# POWER_CORE.net
KiCad netlist of a schematic drawn in Altium Designer
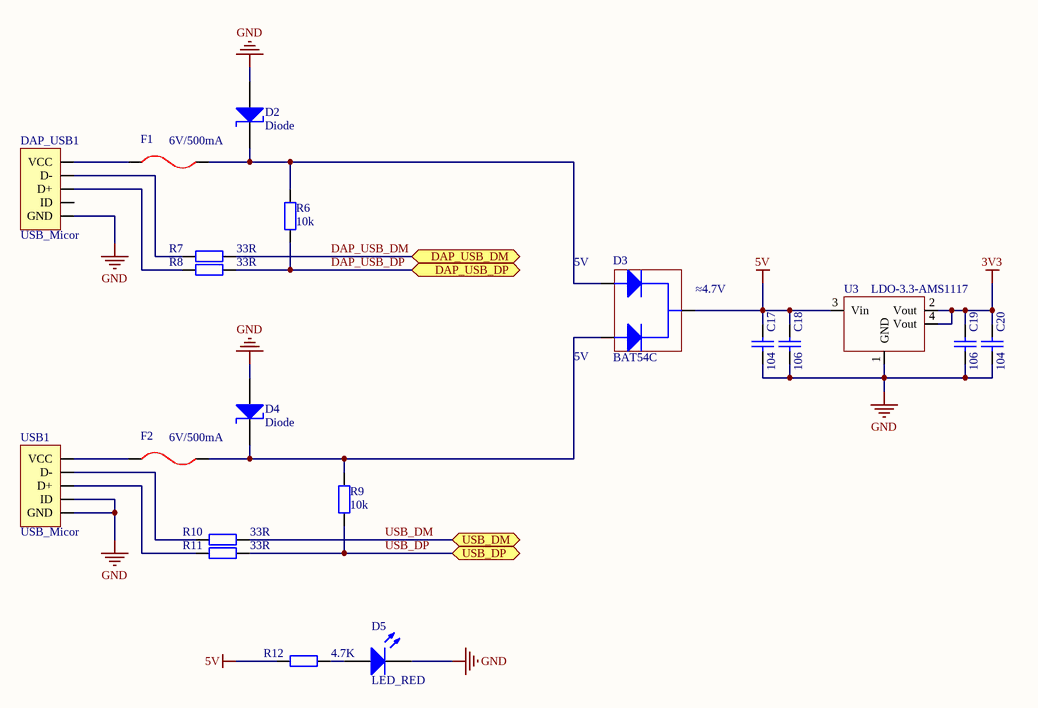
[diagram p0: POWER_CORE.SchDoc]

(export (version "E")
  (design (tool "Eeschema 10.0.6"))
  (components
    (comp (ref "C17")
      (value "104")
      (footprint "C_SOP_0603")
      (description "电容_无极性")
      (libsource (lib "lib-base") (part "Cap"))
    )
    (comp (ref "C18")
      (value "106")
      (footprint "C_SOP_0603")
      (description "电容_无极性")
      (libsource (lib "lib-base") (part "Cap"))
    )
    (comp (ref "C19")
      (value "106")
      (footprint "C_SOP_0603")
      (description "电容_无极性")
      (libsource (lib "lib-base") (part "Cap"))
    )
    (comp (ref "C20")
      (value "104")
      (footprint "C_SOP_0603")
      (description "电容_无极性")
      (libsource (lib "lib-base") (part "Cap"))
    )
    (comp (ref "D2")
      (value "Diode")
      (footprint "SOD-123")
      (description "肖特基二极管\r\n1N4007、SS24")
      (libsource (lib "lib-base") (part "Diode"))
    )
    (comp (ref "D3")
      (value "BAT54C")
      (footprint "SOT23_3")
      (description "肖特基二极管*2")
      (libsource (lib "lib-base") (part "BAT54C"))
    )
    (comp (ref "D4")
      (value "Diode")
      (footprint "SOD-123")
      (description "肖特基二极管\r\n1N4007、SS24")
      (libsource (lib "lib-base") (part "Diode"))
    )
    (comp (ref "D5")
      (value "LED_RED")
      (footprint "LED_0603_R")
      (description "发光二极管")
      (libsource (lib "lib-base") (part "LED"))
    )
    (comp (ref "DAP_USB1")
      (value "USB_Micor")
      (footprint "USB_Micor")
      (libsource (lib "lib-con") (part "USB_Micor"))
    )
    (comp (ref "F1")
      (value "6V/500mA")
      (footprint "FUSE_0603")
      (description "自恢复保险丝")
      (libsource (lib "lib-base") (part "FUSE"))
    )
    (comp (ref "F2")
      (value "6V/500mA")
      (footprint "FUSE_0603")
      (description "自恢复保险丝")
      (libsource (lib "lib-base") (part "FUSE"))
    )
    (comp (ref "R6")
      (value "10k")
      (footprint "R_SMD_0603")
      (description "电阻")
      (libsource (lib "") (part "Res_1"))
    )
    (comp (ref "R7")
      (value "33R")
      (footprint "R_SMD_0603")
      (description "电阻")
      (libsource (lib "lib-base") (part "Res"))
    )
    (comp (ref "R8")
      (value "33R")
      (footprint "R_SMD_0603")
      (description "电阻")
      (libsource (lib "lib-base") (part "Res"))
    )
    (comp (ref "R9")
      (value "10k")
      (footprint "R_SMD_0603")
      (description "电阻")
      (libsource (lib "") (part "Res_1"))
    )
    (comp (ref "R10")
      (value "33R")
      (footprint "R_SMD_0603")
      (description "电阻")
      (libsource (lib "lib-base") (part "Res"))
    )
    (comp (ref "R11")
      (value "33R")
      (footprint "R_SMD_0603")
      (description "电阻")
      (libsource (lib "lib-base") (part "Res"))
    )
    (comp (ref "R12") (value "4.7K") (footprint "R_SMD_0603") (libsource (lib "") (part "Res_2")))
    (comp (ref "U3")
      (value "LDO-3.3-AMS1117")
      (footprint "SOT223_3")
      (description "LDO")
      (libsource (lib "lib-ic") (part "LDO-3.3-AMS1117"))
    )
    (comp (ref "USB1")
      (value "USB_Micor")
      (footprint "USB_Micor")
      (libsource (lib "lib-con") (part "USB_Micor"))
    )
  )
  (nets
    (net (code "1") (name "/DAP_USB_DM") (class "Default")
      (node (ref "R7") (pin "2") (pinfunction "2_2") (pintype "passive"))
    )
    (net (code "2") (name "/DAP_USB_DP") (class "Default")
      (node (ref "R6") (pin "1") (pinfunction "1_1") (pintype "passive"))
      (node (ref "R8") (pin "2") (pinfunction "2_2") (pintype "passive"))
    )
    (net (code "3") (name "/USB_DM") (class "Default")
      (node (ref "R10") (pin "2") (pinfunction "2_2") (pintype "passive"))
    )
    (net (code "4") (name "/USB_DP") (class "Default")
      (node (ref "R11") (pin "2") (pinfunction "2_2") (pintype "passive"))
      (node (ref "R9") (pin "1") (pinfunction "1_1") (pintype "passive"))
    )
    (net (code "5") (name "3V3") (class "Default")
      (node (ref "C19") (pin "2") (pinfunction "2_2") (pintype "passive"))
      (node (ref "C20") (pin "2") (pinfunction "2_2") (pintype "passive"))
      (node (ref "U3") (pin "2") (pinfunction "Vout_2") (pintype "passive"))
      (node (ref "U3") (pin "4") (pinfunction "Vout_4") (pintype "passive"))
    )
    (net (code "6") (name "5V") (class "Default")
      (node (ref "C17") (pin "2") (pinfunction "2_2") (pintype "passive"))
      (node (ref "C18") (pin "2") (pinfunction "2_2") (pintype "passive"))
      (node (ref "D3") (pin "3") (pinfunction "3_3") (pintype "passive"))
      (node (ref "R12") (pin "2") (pinfunction "2_2") (pintype "passive"))
      (node (ref "U3") (pin "3") (pinfunction "Vin_3") (pintype "passive"))
    )
    (net (code "7") (name "GND") (class "Default")
      (node (ref "C17") (pin "1") (pinfunction "1_1") (pintype "passive"))
      (node (ref "C18") (pin "1") (pinfunction "1_1") (pintype "passive"))
      (node (ref "C19") (pin "1") (pinfunction "1_1") (pintype "passive"))
      (node (ref "C20") (pin "1") (pinfunction "1_1") (pintype "passive"))
      (node (ref "D2") (pin "1") (pinfunction "A_1") (pintype "passive"))
      (node (ref "D4") (pin "1") (pinfunction "A_1") (pintype "passive"))
      (node (ref "D5") (pin "2") (pinfunction "K_2") (pintype "passive"))
      (node (ref "DAP_USB1") (pin "5") (pinfunction "GND_5") (pintype "passive"))
      (node (ref "U3") (pin "1") (pinfunction "GND_1") (pintype "passive"))
      (node (ref "USB1") (pin "4") (pinfunction "ID_4") (pintype "passive"))
      (node (ref "USB1") (pin "5") (pinfunction "GND_5") (pintype "passive"))
    )
    (net (code "8") (name "Net-(D2-K)") (class "Default")
      (node (ref "D2") (pin "2") (pinfunction "K_2") (pintype "passive"))
      (node (ref "D3") (pin "1") (pinfunction "1_1") (pintype "passive"))
      (node (ref "F1") (pin "2") (pinfunction "2_2") (pintype "passive"))
      (node (ref "R6") (pin "2") (pinfunction "2_2") (pintype "passive"))
    )
    (net (code "9") (name "Net-(D4-K)") (class "Default")
      (node (ref "D3") (pin "2") (pinfunction "2_2") (pintype "passive"))
      (node (ref "D4") (pin "2") (pinfunction "K_2") (pintype "passive"))
      (node (ref "F2") (pin "2") (pinfunction "2_2") (pintype "passive"))
      (node (ref "R9") (pin "2") (pinfunction "2_2") (pintype "passive"))
    )
    (net (code "10") (name "Net-(D5-A)") (class "Default")
      (node (ref "D5") (pin "1") (pinfunction "A_1") (pintype "passive"))
      (node (ref "R12") (pin "1") (pinfunction "1_1") (pintype "passive"))
    )
    (net (code "11") (name "Net-(DAP_USB1-D+)") (class "Default")
      (node (ref "DAP_USB1") (pin "3") (pinfunction "D+_3") (pintype "passive"))
      (node (ref "R8") (pin "1") (pinfunction "1_1") (pintype "passive"))
    )
    (net (code "12") (name "Net-(DAP_USB1-D-)") (class "Default")
      (node (ref "DAP_USB1") (pin "2") (pinfunction "D-_2") (pintype "passive"))
      (node (ref "R7") (pin "1") (pinfunction "1_1") (pintype "passive"))
    )
    (net (code "13") (name "Net-(DAP_USB1-VCC)") (class "Default")
      (node (ref "DAP_USB1") (pin "1") (pinfunction "VCC_1") (pintype "passive"))
      (node (ref "F1") (pin "1") (pinfunction "1_1") (pintype "passive"))
    )
    (net (code "14") (name "Net-(USB1-D+)") (class "Default")
      (node (ref "R11") (pin "1") (pinfunction "1_1") (pintype "passive"))
      (node (ref "USB1") (pin "3") (pinfunction "D+_3") (pintype "passive"))
    )
    (net (code "15") (name "Net-(USB1-D-)") (class "Default")
      (node (ref "R10") (pin "1") (pinfunction "1_1") (pintype "passive"))
      (node (ref "USB1") (pin "2") (pinfunction "D-_2") (pintype "passive"))
    )
    (net (code "16") (name "Net-(USB1-VCC)") (class "Default")
      (node (ref "F2") (pin "1") (pinfunction "1_1") (pintype "passive"))
      (node (ref "USB1") (pin "1") (pinfunction "VCC_1") (pintype "passive"))
    )
    (net (code "17") (name "unconnected-(DAP_USB1-ID-Pad4)") (class "Default")
      (node (ref "DAP_USB1") (pin "4") (pinfunction "ID_4") (pintype "passive"))
    )
  )
)
